# FORCE_SENSOR.net
KiCad netlist of a schematic drawn in EAGLE
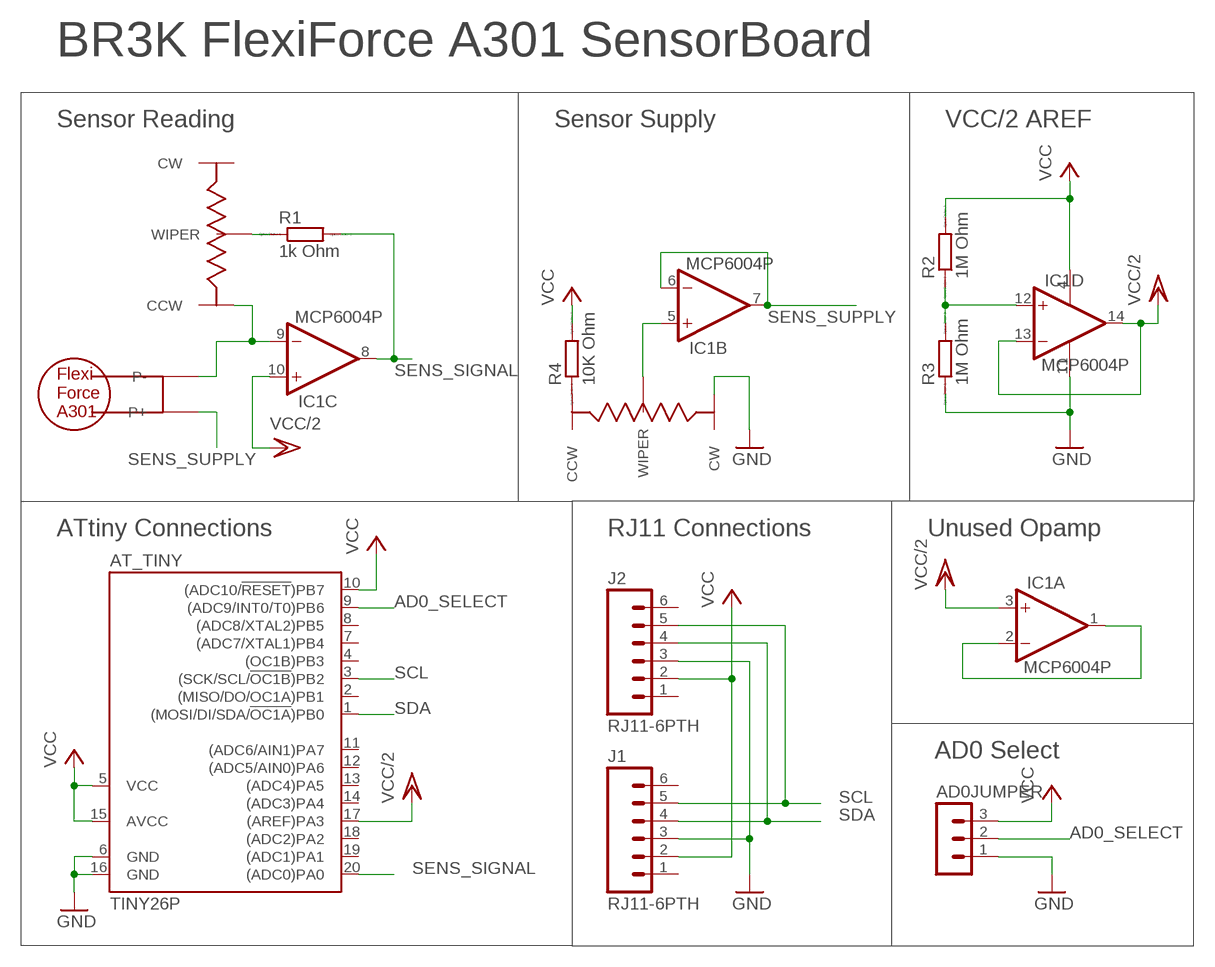
[diagram p0: schematic, sheet 1]

(export (version "E")
  (design (tool "Eeschema 10.0.6"))
  (components
    (comp (ref "AD0JUMPER")
      (value "MA03-1")
      (footprint "eagle-import:MA03-1")
      (libsource (lib "eagle-import") (part "MA03-1"))
    )
    (comp (ref "AT_TINY")
      (value "TINY26P")
      (footprint "eagle-import:DIL20")
      (fields (field (name "MPN") "ATTINY261-20PU"))
      (libsource (lib "eagle-import") (part "TINY26P"))
    )
    (comp (ref "IC1")
      (value "MCP6004P")
      (footprint "eagle-import:DIL14")
      (libsource (lib "eagle-import") (part "MCP6004P"))
    )
    (comp (ref "J1")
      (value "RJ11-6PTH")
      (footprint "eagle-import:RJ11-6")
      (libsource (lib "eagle-import") (part "RJ11-6PTH"))
    )
    (comp (ref "J2")
      (value "RJ11-6PTH")
      (footprint "eagle-import:RJ11-6")
      (libsource (lib "eagle-import") (part "RJ11-6PTH"))
    )
    (comp (ref "R1")
      (value "1k Ohm")
      (footprint "eagle-import:0207_10")
      (libsource (lib "eagle-import") (part "R-EU_0207_10"))
    )
    (comp (ref "R2")
      (value "1M Ohm")
      (footprint "eagle-import:0207_10")
      (libsource (lib "eagle-import") (part "R-EU_0207_10"))
    )
    (comp (ref "R3")
      (value "1M Ohm")
      (footprint "eagle-import:0207_10")
      (libsource (lib "eagle-import") (part "R-EU_0207_10"))
    )
    (comp (ref "R4")
      (value "10K Ohm")
      (footprint "eagle-import:0207_10")
      (libsource (lib "eagle-import") (part "R-EU_0207_10"))
    )
    (comp (ref "U$1")
      (value "FLEXI_FORCE_A301")
      (footprint "eagle-import:FLEXIFORCE_W237-102")
      (libsource (lib "eagle-import") (part "FLEXI_FORCE_A301"))
    )
    (comp (ref "U$2")
      (value "100k Ohm")
      (footprint "eagle-import:VERT_TRIMPOT")
      (libsource (lib "eagle-import") (part "TRIMMER_3296"))
    )
    (comp (ref "U$3")
      (value "10k Ohm")
      (footprint "eagle-import:VERT_TRIMPOT")
      (libsource (lib "eagle-import") (part "TRIMMER_3296"))
    )
  )
  (nets
    (net (code "1") (name "/AD0_SELECT") (class "Default")
      (node (ref "AD0JUMPER") (pin "2") (pinfunction "2_2") (pintype "passive"))
      (node (ref "AT_TINY") (pin "9") (pinfunction "(ADC9/INT0/T0)PB6_9") (pintype "bidirectional"))
    )
    (net (code "2") (name "/SCL") (class "Default")
      (node (ref "AT_TINY") (pin "3") (pinfunction "(SCK/SCL/~{OC1B})PB2_3") (pintype "bidirectional"))
      (node (ref "J1") (pin "5") (pinfunction "5_5") (pintype "passive"))
      (node (ref "J2") (pin "5") (pinfunction "5_5") (pintype "passive"))
    )
    (net (code "3") (name "/SDA") (class "Default")
      (node (ref "AT_TINY") (pin "1") (pinfunction "(MOSI/DI/SDA/~{OC1A})PB0_1") (pintype "bidirectional"))
      (node (ref "J1") (pin "4") (pinfunction "4_4") (pintype "passive"))
      (node (ref "J2") (pin "4") (pinfunction "4_4") (pintype "passive"))
    )
    (net (code "4") (name "/SENS_SIGNAL") (class "Default")
      (node (ref "AT_TINY") (pin "20") (pinfunction "(ADC0)PA0_20") (pintype "bidirectional"))
      (node (ref "IC1") (pin "8") (pinfunction "OUT_8") (pintype "output"))
      (node (ref "R1") (pin "2") (pinfunction "2_2") (pintype "passive"))
    )
    (net (code "5") (name "/SENS_SUPPLY") (class "Default")
      (node (ref "IC1") (pin "6") (pinfunction "-IN_6") (pintype "input"))
      (node (ref "IC1") (pin "7") (pinfunction "OUT_7") (pintype "output"))
      (node (ref "U$1") (pin "1") (pinfunction "P+_1") (pintype "bidirectional"))
    )
    (net (code "6") (name "GND") (class "Default")
      (node (ref "AD0JUMPER") (pin "1") (pinfunction "1_1") (pintype "passive"))
      (node (ref "AT_TINY") (pin "16") (pinfunction "GND_16") (pintype "power_in"))
      (node (ref "AT_TINY") (pin "6") (pinfunction "GND_6") (pintype "power_in"))
      (node (ref "IC1") (pin "11") (pinfunction "V-_11") (pintype "power_in"))
      (node (ref "J1") (pin "3") (pinfunction "3_3") (pintype "passive"))
      (node (ref "J2") (pin "3") (pinfunction "3_3") (pintype "passive"))
      (node (ref "R3") (pin "1") (pinfunction "1_1") (pintype "passive"))
      (node (ref "U$3") (pin "CW") (pinfunction "CW_CW") (pintype "bidirectional"))
    )
    (net (code "7") (name "Net-(IC1A--IN)") (class "Default")
      (node (ref "IC1") (pin "1") (pinfunction "OUT_1") (pintype "output"))
      (node (ref "IC1") (pin "2") (pinfunction "-IN_2") (pintype "input"))
    )
    (net (code "8") (name "Net-(IC1B-+IN)") (class "Default")
      (node (ref "IC1") (pin "5") (pinfunction "+IN_5") (pintype "input"))
      (node (ref "U$3") (pin "WIP") (pinfunction "WIPER_WIP") (pintype "bidirectional"))
    )
    (net (code "9") (name "Net-(IC1C--IN)") (class "Default")
      (node (ref "IC1") (pin "9") (pinfunction "-IN_9") (pintype "input"))
      (node (ref "U$1") (pin "2") (pinfunction "P-_2") (pintype "bidirectional"))
      (node (ref "U$2") (pin "CCW") (pinfunction "CCW_CCW") (pintype "bidirectional"))
    )
    (net (code "10") (name "Net-(IC1D-+IN)") (class "Default")
      (node (ref "IC1") (pin "12") (pinfunction "+IN_12") (pintype "input"))
      (node (ref "R2") (pin "1") (pinfunction "1_1") (pintype "passive"))
      (node (ref "R3") (pin "2") (pinfunction "2_2") (pintype "passive"))
    )
    (net (code "11") (name "Net-(R4-Pad1)") (class "Default")
      (node (ref "R4") (pin "1") (pinfunction "1_1") (pintype "passive"))
      (node (ref "U$3") (pin "CCW") (pinfunction "CCW_CCW") (pintype "bidirectional"))
    )
    (net (code "12") (name "Net-(U$2-WIPER)") (class "Default")
      (node (ref "R1") (pin "1") (pinfunction "1_1") (pintype "passive"))
      (node (ref "U$2") (pin "WIP") (pinfunction "WIPER_WIP") (pintype "bidirectional"))
    )
    (net (code "13") (name "VCC") (class "Default")
      (node (ref "AD0JUMPER") (pin "3") (pinfunction "3_3") (pintype "passive"))
      (node (ref "AT_TINY") (pin "10") (pinfunction "(ADC10/~{RESET})PB7_10") (pintype "bidirectional"))
      (node (ref "AT_TINY") (pin "15") (pinfunction "AVCC_15") (pintype "power_in"))
      (node (ref "AT_TINY") (pin "5") (pinfunction "VCC_5") (pintype "power_in"))
      (node (ref "IC1") (pin "4") (pinfunction "V+_4") (pintype "power_in"))
      (node (ref "J1") (pin "2") (pinfunction "2_2") (pintype "passive"))
      (node (ref "J2") (pin "2") (pinfunction "2_2") (pintype "passive"))
      (node (ref "R2") (pin "2") (pinfunction "2_2") (pintype "passive"))
      (node (ref "R4") (pin "2") (pinfunction "2_2") (pintype "passive"))
    )
    (net (code "14") (name "VCC{slash}2") (class "Default")
      (node (ref "AT_TINY") (pin "17") (pinfunction "(AREF)PA3_17") (pintype "bidirectional"))
      (node (ref "IC1") (pin "10") (pinfunction "+IN_10") (pintype "input"))
      (node (ref "IC1") (pin "13") (pinfunction "-IN_13") (pintype "input"))
      (node (ref "IC1") (pin "14") (pinfunction "OUT_14") (pintype "output"))
      (node (ref "IC1") (pin "3") (pinfunction "+IN_3") (pintype "input"))
    )
    (net (code "15") (name "unconnected-(AT_TINY-(ADC1)PA1-Pad19)") (class "Default")
      (node (ref "AT_TINY") (pin "19") (pinfunction "(ADC1)PA1_19") (pintype "bidirectional"))
    )
    (net (code "16") (name "unconnected-(AT_TINY-(ADC2)PA2-Pad18)") (class "Default")
      (node (ref "AT_TINY") (pin "18") (pinfunction "(ADC2)PA2_18") (pintype "bidirectional"))
    )
    (net (code "17") (name "unconnected-(AT_TINY-(ADC3)PA4-Pad14)") (class "Default")
      (node (ref "AT_TINY") (pin "14") (pinfunction "(ADC3)PA4_14") (pintype "bidirectional"))
    )
    (net (code "18") (name "unconnected-(AT_TINY-(ADC4)PA5-Pad13)") (class "Default")
      (node (ref "AT_TINY") (pin "13") (pinfunction "(ADC4)PA5_13") (pintype "bidirectional"))
    )
    (net (code "19") (name "unconnected-(AT_TINY-(ADC5{slash}AIN0)PA6-Pad12)") (class "Default")
      (node (ref "AT_TINY") (pin "12") (pinfunction "(ADC5/AIN0)PA6_12") (pintype "bidirectional"))
    )
    (net (code "20") (name "unconnected-(AT_TINY-(ADC6{slash}AIN1)PA7-Pad11)") (class "Default")
      (node (ref "AT_TINY") (pin "11") (pinfunction "(ADC6/AIN1)PA7_11") (pintype "bidirectional"))
    )
    (net (code "21") (name "unconnected-(AT_TINY-(ADC7{slash}XTAL1)PB4-Pad7)") (class "Default")
      (node (ref "AT_TINY") (pin "7") (pinfunction "(ADC7/XTAL1)PB4_7") (pintype "bidirectional"))
    )
    (net (code "22") (name "unconnected-(AT_TINY-(ADC8{slash}XTAL2)PB5-Pad8)") (class "Default")
      (node (ref "AT_TINY") (pin "8") (pinfunction "(ADC8/XTAL2)PB5_8") (pintype "bidirectional"))
    )
    (net (code "23") (name "unconnected-(AT_TINY-(MISO{slash}DO{slash}OC1A)PB1-Pad2)") (class "Default")
      (node (ref "AT_TINY") (pin "2") (pinfunction "(MISO/DO/OC1A)PB1_2") (pintype "bidirectional"))
    )
    (net (code "24") (name "unconnected-(AT_TINY-(OC1B)PB3-Pad4)") (class "Default")
      (node (ref "AT_TINY") (pin "4") (pinfunction "(OC1B)PB3_4") (pintype "bidirectional"))
    )
    (net (code "25") (name "unconnected-(J1-Pad1)") (class "Default")
      (node (ref "J1") (pin "1") (pinfunction "1_1") (pintype "passive"))
    )
    (net (code "26") (name "unconnected-(J1-Pad6)") (class "Default")
      (node (ref "J1") (pin "6") (pinfunction "6_6") (pintype "passive"))
    )
    (net (code "27") (name "unconnected-(J2-Pad1)") (class "Default")
      (node (ref "J2") (pin "1") (pinfunction "1_1") (pintype "passive"))
    )
    (net (code "28") (name "unconnected-(J2-Pad6)") (class "Default")
      (node (ref "J2") (pin "6") (pinfunction "6_6") (pintype "passive"))
    )
    (net (code "29") (name "unconnected-(U$2-PadCW)") (class "Default")
      (node (ref "U$2") (pin "CW") (pinfunction "CW_CW") (pintype "bidirectional"))
    )
  )
)
